# HU_MAIN_PCB_revA.net
KiCad netlist of a schematic drawn in Altium Designer
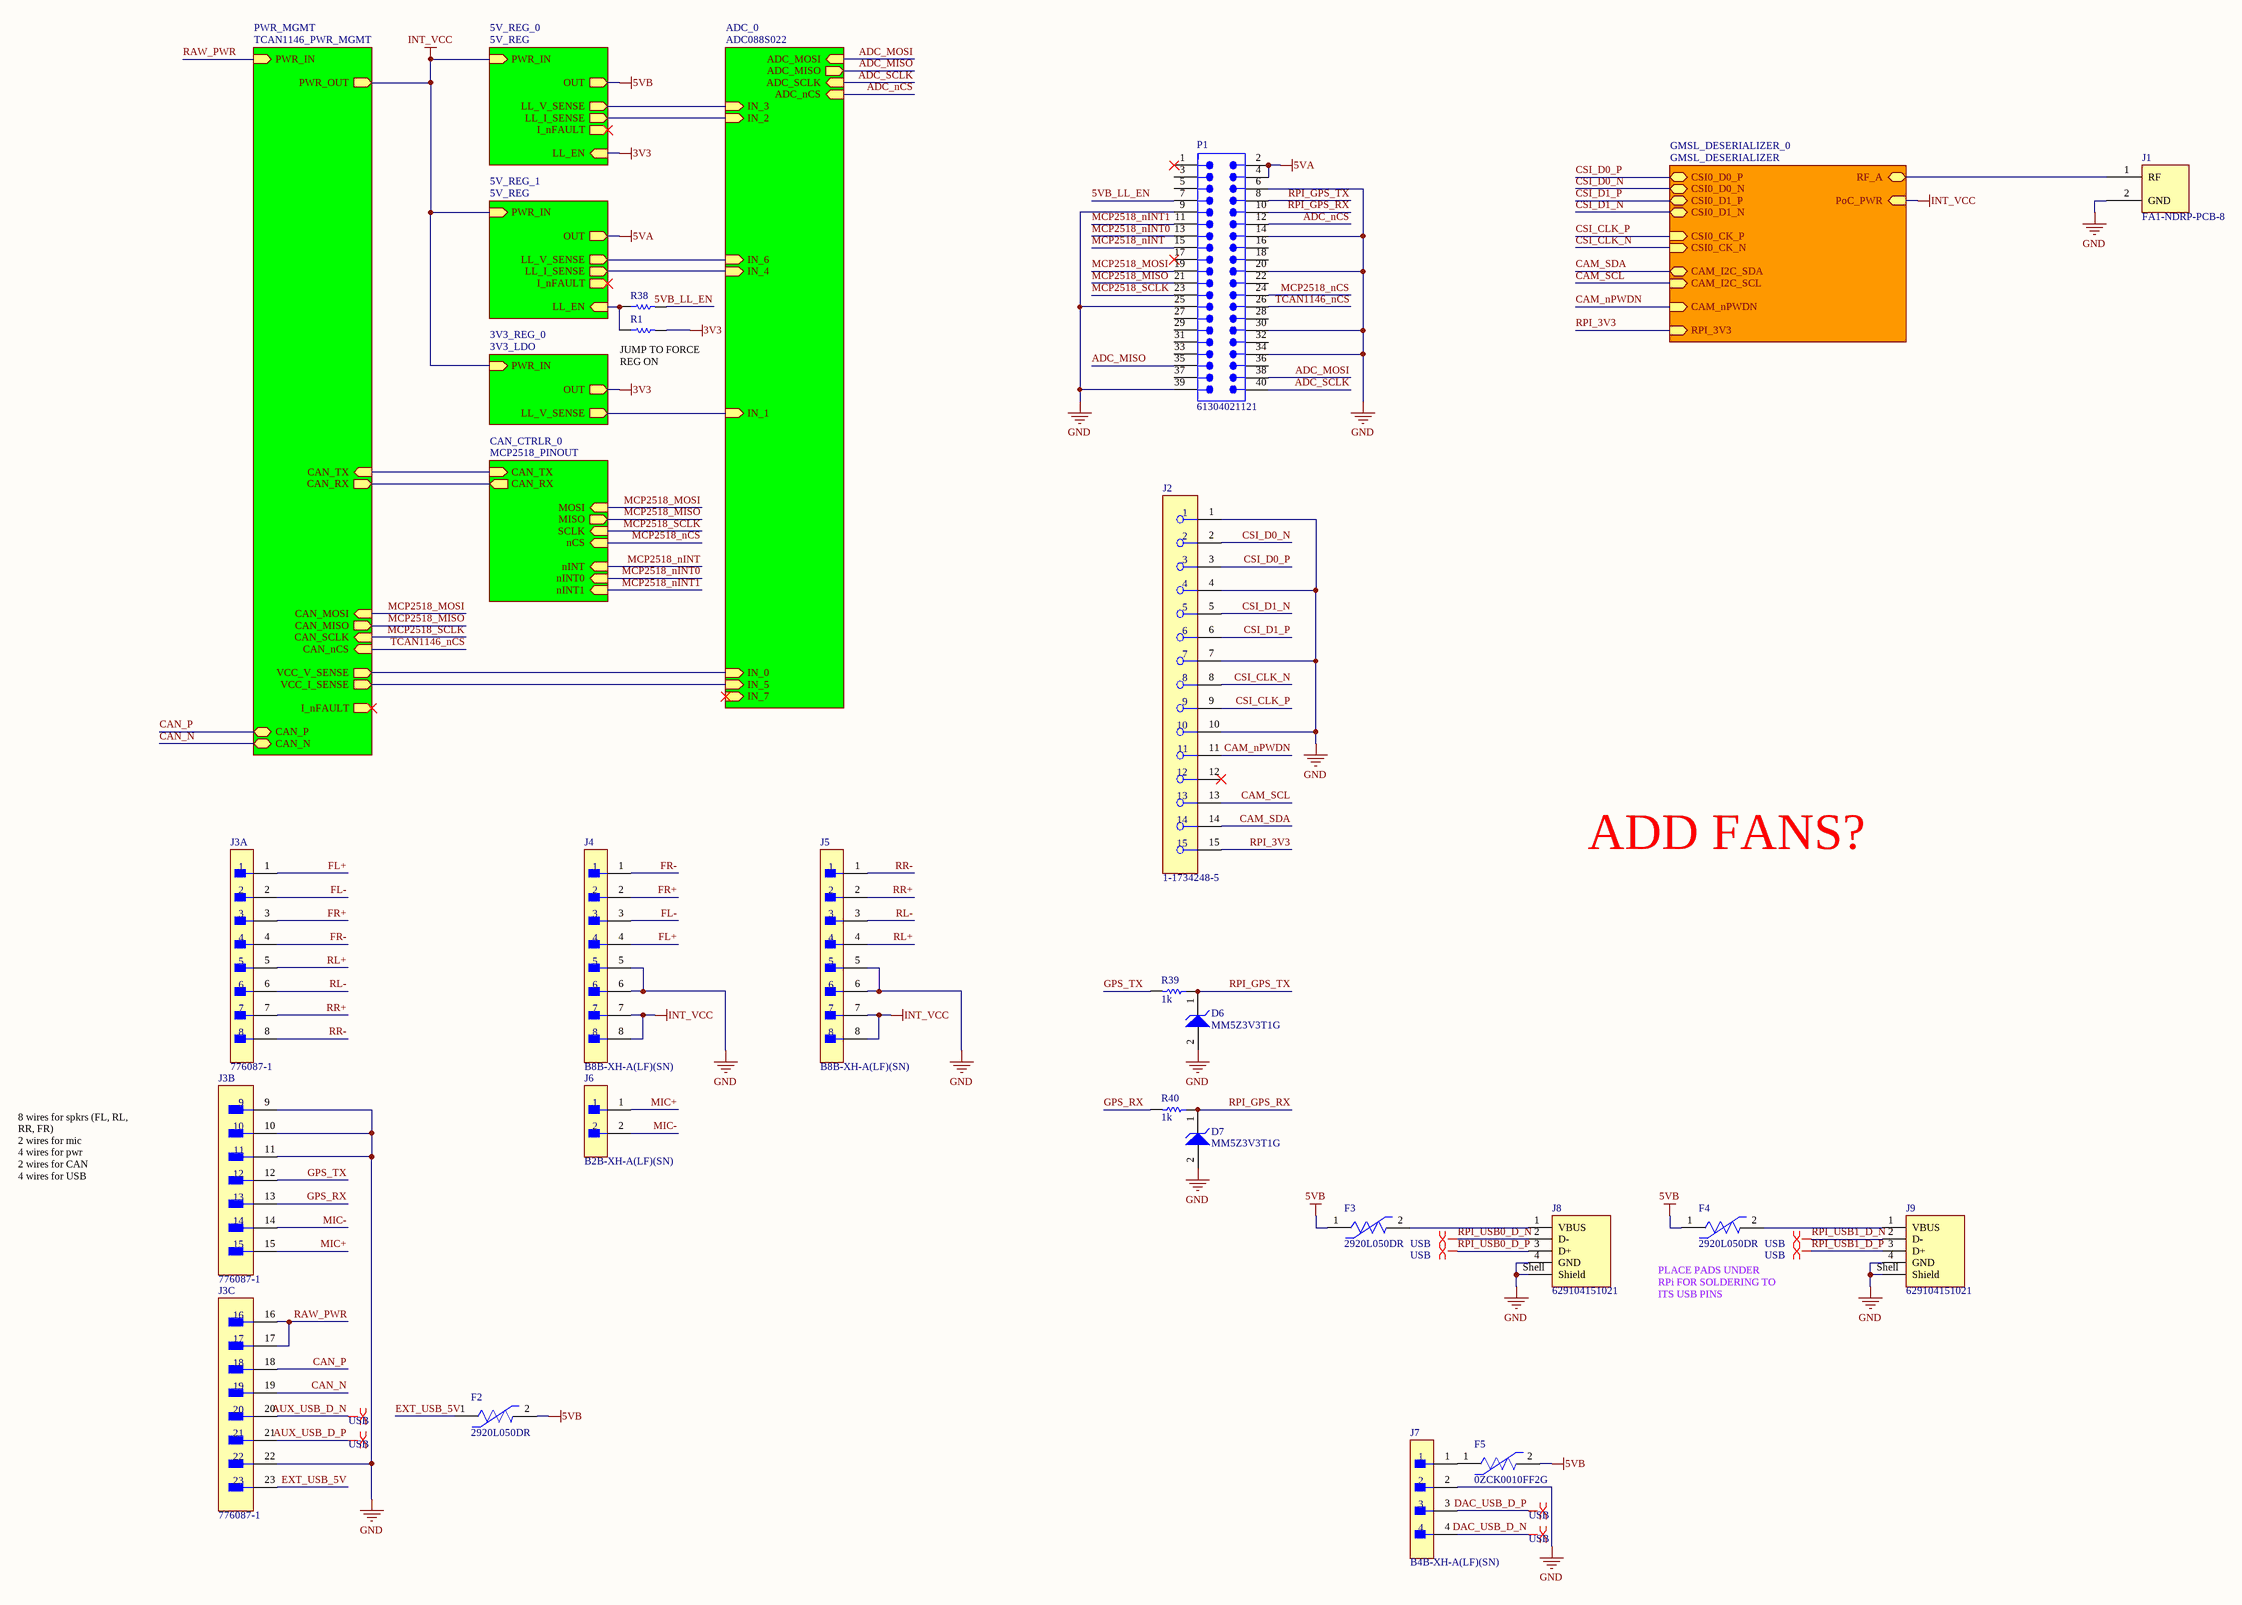
[diagram p0: HU_MAIN_PCB_revA.SchDoc]

(export (version "E")
  (design (tool "Eeschema 10.0.6"))
  (components
    (comp (ref "D6")
      (value "MM5Z3V3T1G")
      (footprint "ONSC-SOD-523-2-502-01_V")
      (description "Zener Voltage Regulator, 500 mW, 2-Pin SOD-523, Pb-Free, Tape and Reel")
      (fields (field (name "MANUFACTURER") "On Semiconductor"))
      (libsource (lib "Altium Content Vault") (part "ONSC-K1A2-2"))
    )
    (comp (ref "D7")
      (value "MM5Z3V3T1G")
      (footprint "ONSC-SOD-523-2-502-01_V")
      (description "Zener Voltage Regulator, 500 mW, 2-Pin SOD-523, Pb-Free, Tape and Reel")
      (fields (field (name "MANUFACTURER") "On Semiconductor"))
      (libsource (lib "Altium Content Vault") (part "ONSC-K1A2-2"))
    )
    (comp (ref "F2")
      (value "2920L050DR")
      (footprint "FP-2920L050DR-MFG")
      (description "PTC RESET FUSE 60V 500MA 2920")
      (libsource (lib "Altium Content Vault") (part "1c6d77a0208143737455a0c7eb396be"))
    )
    (comp (ref "F3")
      (value "2920L050DR")
      (footprint "FP-2920L050DR-MFG")
      (description "PTC RESET FUSE 60V 500MA 2920")
      (libsource (lib "Altium Content Vault") (part "1c6d77a0208143737455a0c7eb396be"))
    )
    (comp (ref "F4")
      (value "2920L050DR")
      (footprint "FP-2920L050DR-MFG")
      (description "PTC RESET FUSE 60V 500MA 2920")
      (libsource (lib "Altium Content Vault") (part "1c6d77a0208143737455a0c7eb396be"))
    )
    (comp (ref "F5")
      (value "0ZCK0010FF2G")
      (footprint "FP-0ZCK0010FF2G-MFG")
      (description "PTC RESET FUSE 15V 100MA 0805")
      (libsource (lib "Altium Content Vault") (part "fc31388045fc42ab786d6d00b506e9f"))
    )
    (comp (ref "J1")
      (value "FA1-NDRP-PCB-8")
      (footprint "FA1-NDRP-PCB-8-Footprint-1")
      (description "RF F Connector, Male, Board Mount, Solder Terminal, Plug")
      (libsource (lib "Space Concordia") (part "FA1-NDRP-PCB-8"))
    )
    (comp (ref "J2")
      (value "1-1734248-5")
      (footprint "FP-1-1734248-5-MFG")
      (description "CONN FPC VERT 15POS 1.00MM SMD")
      (fields
        (field (name "MANUFACTURER") "TE")
        (field (name "OCTOPART") "https://octopart.com/1-1734248-5-te+connectivity-40620898")
      )
      (libsource (lib "Altium Content Vault") (part "a0777be16b290adccad2a8f9338c195"))
    )
    (comp (ref "J3")
      (value "776087-1")
      (footprint "FP-776087-1-MFG")
      (description "CONN HEADER R/A 23POS 4MM")
      (libsource (lib "Altium Content Vault") (part "1cdbe6524175775e54446a79a4f0ed8"))
    )
    (comp (ref "J4")
      (value "B8B-XH-A(LF)(SN)")
      (footprint "FP-B8B-XH-A_LF_SN-MFG")
      (description "CONN HEADER VERT 8POS 2.5MM")
      (libsource (lib "Altium Content Vault") (part "99ec2b232beb5d2356d4d77f6a047f0"))
    )
    (comp (ref "J5")
      (value "B8B-XH-A(LF)(SN)")
      (footprint "FP-B8B-XH-A_LF_SN-MFG")
      (description "CONN HEADER VERT 8POS 2.5MM")
      (libsource (lib "Altium Content Vault") (part "99ec2b232beb5d2356d4d77f6a047f0"))
    )
    (comp (ref "J6")
      (value "B2B-XH-A(LF)(SN)")
      (footprint "FP-B2B-XH-A_LF_SN-MFG")
      (description "CONN HEADER VERT 2POS 2.5MM")
      (libsource (lib "Altium Content Vault") (part "3bc925449376181038e59eaffc5286c"))
    )
    (comp (ref "J7")
      (value "B4B-XH-A(LF)(SN)")
      (footprint "FP-B4B-XH-A_LF_SN-MFG")
      (description "CONN HEADER VERT 4POS 2.5MM")
      (libsource (lib "Altium Content Vault") (part "299a8cea1bdcbc3624fe62c390fa72c"))
    )
    (comp (ref "J8")
      (value "629104151021")
      (footprint "629104151021")
      (libsource (lib "Altium Content Vault") (part "USB 2.0_Type A_Receptacle_1 Port"))
    )
    (comp (ref "J9")
      (value "629104151021")
      (footprint "629104151021")
      (libsource (lib "Altium Content Vault") (part "USB 2.0_Type A_Receptacle_1 Port"))
    )
    (comp (ref "P1")
      (value "61304021121")
      (footprint "61304021121")
      (libsource (lib "Altium Content Vault") (part "Header_Male_2R_40P"))
    )
    (comp (ref "R1")
      (value "DNP")
      (footprint "RESC1005X40X25ML05T05")
      (description "READ THE NAME")
      (libsource (lib "Space Concordia") (part "CMP-009-00206-2"))
    )
    (comp (ref "R38")
      (value "DNP")
      (footprint "RESC1005X40X25ML05T05")
      (description "READ THE NAME")
      (libsource (lib "Space Concordia") (part "CMP-009-00206-2"))
    )
    (comp (ref "R39")
      (value "1k")
      (footprint "R0603B")
      (description "Resistor")
      (libsource (lib "Space Concordia") (part "Resistor"))
    )
    (comp (ref "R40")
      (value "1k")
      (footprint "R0603B")
      (description "Resistor")
      (libsource (lib "Space Concordia") (part "Resistor"))
    )
  )
  (nets
    (net (code "1") (name "/5VB_LL_EN") (class "Default")
      (node (ref "P1") (pin "7") (pinfunction "7_7") (pintype "passive"))
      (node (ref "R38") (pin "2") (pinfunction "2_2") (pintype "passive"))
    )
    (net (code "2") (name "/ADC_MISO") (class "Default")
      (node (ref "P1") (pin "35") (pinfunction "35_35") (pintype "passive"))
    )
    (net (code "3") (name "/ADC_MOSI") (class "Default")
      (node (ref "P1") (pin "38") (pinfunction "38_38") (pintype "passive"))
    )
    (net (code "4") (name "/ADC_SCLK") (class "Default")
      (node (ref "P1") (pin "40") (pinfunction "40_40") (pintype "passive"))
    )
    (net (code "5") (name "/ADC_nCS") (class "Default")
      (node (ref "P1") (pin "12") (pinfunction "12_12") (pintype "passive"))
    )
    (net (code "6") (name "/AUX_USB_D_N") (class "Default")
      (node (ref "J3") (pin "20") (pinfunction "20_20") (pintype "passive"))
    )
    (net (code "7") (name "/AUX_USB_D_P") (class "Default")
      (node (ref "J3") (pin "21") (pinfunction "21_21") (pintype "passive"))
    )
    (net (code "8") (name "/CAM_SCL") (class "Default")
      (node (ref "J2") (pin "13") (pinfunction "13_13") (pintype "passive"))
    )
    (net (code "9") (name "/CAM_SDA") (class "Default")
      (node (ref "J2") (pin "14") (pinfunction "14_14") (pintype "passive"))
    )
    (net (code "10") (name "/CAM_nPWDN") (class "Default")
      (node (ref "J2") (pin "11") (pinfunction "11_11") (pintype "passive"))
    )
    (net (code "11") (name "/CAN_N") (class "Default")
      (node (ref "J3") (pin "19") (pinfunction "19_19") (pintype "passive"))
    )
    (net (code "12") (name "/CAN_P") (class "Default")
      (node (ref "J3") (pin "18") (pinfunction "18_18") (pintype "passive"))
    )
    (net (code "15") (name "/CSI_CLK_N") (class "Default")
      (node (ref "J2") (pin "8") (pinfunction "8_8") (pintype "passive"))
    )
    (net (code "16") (name "/CSI_CLK_P") (class "Default")
      (node (ref "J2") (pin "9") (pinfunction "9_9") (pintype "passive"))
    )
    (net (code "17") (name "/CSI_D0_N") (class "Default")
      (node (ref "J2") (pin "2") (pinfunction "2_2") (pintype "passive"))
    )
    (net (code "18") (name "/CSI_D0_P") (class "Default")
      (node (ref "J2") (pin "3") (pinfunction "3_3") (pintype "passive"))
    )
    (net (code "19") (name "/CSI_D1_N") (class "Default")
      (node (ref "J2") (pin "5") (pinfunction "5_5") (pintype "passive"))
    )
    (net (code "20") (name "/CSI_D1_P") (class "Default")
      (node (ref "J2") (pin "6") (pinfunction "6_6") (pintype "passive"))
    )
    (net (code "21") (name "/DAC_USB_D_N") (class "Default")
      (node (ref "J7") (pin "4") (pinfunction "4_4") (pintype "passive"))
    )
    (net (code "22") (name "/DAC_USB_D_P") (class "Default")
      (node (ref "J7") (pin "3") (pinfunction "3_3") (pintype "passive"))
    )
    (net (code "23") (name "/EXT_USB_5V") (class "Default")
      (node (ref "F2") (pin "1") (pinfunction "1_1") (pintype "passive"))
      (node (ref "J3") (pin "23") (pinfunction "23_23") (pintype "passive"))
    )
    (net (code "24") (name "/FL+") (class "Default")
      (node (ref "J3") (pin "1") (pinfunction "1_1") (pintype "passive"))
      (node (ref "J4") (pin "4") (pinfunction "4_4") (pintype "passive"))
    )
    (net (code "25") (name "/FL-") (class "Default")
      (node (ref "J3") (pin "2") (pinfunction "2_2") (pintype "passive"))
      (node (ref "J4") (pin "3") (pinfunction "3_3") (pintype "passive"))
    )
    (net (code "26") (name "/FR+") (class "Default")
      (node (ref "J3") (pin "3") (pinfunction "3_3") (pintype "passive"))
      (node (ref "J4") (pin "2") (pinfunction "2_2") (pintype "passive"))
    )
    (net (code "27") (name "/FR-") (class "Default")
      (node (ref "J3") (pin "4") (pinfunction "4_4") (pintype "passive"))
      (node (ref "J4") (pin "1") (pinfunction "1_1") (pintype "passive"))
    )
    (net (code "28") (name "/GPS_RX") (class "Default")
      (node (ref "J3") (pin "13") (pinfunction "13_13") (pintype "passive"))
      (node (ref "R40") (pin "2") (pinfunction "2_2") (pintype "passive"))
    )
    (net (code "29") (name "/GPS_TX") (class "Default")
      (node (ref "J3") (pin "12") (pinfunction "12_12") (pintype "passive"))
      (node (ref "R39") (pin "2") (pinfunction "2_2") (pintype "passive"))
    )
    (net (code "34") (name "/LL_EN") (class "Default")
      (node (ref "R1") (pin "1") (pinfunction "1_1") (pintype "passive"))
      (node (ref "R38") (pin "1") (pinfunction "1_1") (pintype "passive"))
    )
    (net (code "40") (name "/MCP2518_MISO") (class "Default")
      (node (ref "P1") (pin "21") (pinfunction "21_21") (pintype "passive"))
    )
    (net (code "41") (name "/MCP2518_MOSI") (class "Default")
      (node (ref "P1") (pin "19") (pinfunction "19_19") (pintype "passive"))
    )
    (net (code "42") (name "/MCP2518_SCLK") (class "Default")
      (node (ref "P1") (pin "23") (pinfunction "23_23") (pintype "passive"))
    )
    (net (code "43") (name "/MCP2518_nCS") (class "Default")
      (node (ref "P1") (pin "24") (pinfunction "24_24") (pintype "passive"))
    )
    (net (code "44") (name "/MCP2518_nINT") (class "Default")
      (node (ref "P1") (pin "15") (pinfunction "15_15") (pintype "passive"))
    )
    (net (code "45") (name "/MCP2518_nINT0") (class "Default")
      (node (ref "P1") (pin "13") (pinfunction "13_13") (pintype "passive"))
    )
    (net (code "46") (name "/MCP2518_nINT1") (class "Default")
      (node (ref "P1") (pin "11") (pinfunction "11_11") (pintype "passive"))
    )
    (net (code "47") (name "/MIC+") (class "Default")
      (node (ref "J3") (pin "15") (pinfunction "15_15") (pintype "passive"))
      (node (ref "J6") (pin "1") (pinfunction "1_1") (pintype "passive"))
    )
    (net (code "48") (name "/MIC-") (class "Default")
      (node (ref "J3") (pin "14") (pinfunction "14_14") (pintype "passive"))
      (node (ref "J6") (pin "2") (pinfunction "2_2") (pintype "passive"))
    )
    (net (code "49") (name "/RAW_PWR") (class "Default")
      (node (ref "J3") (pin "16") (pinfunction "16_16") (pintype "passive"))
      (node (ref "J3") (pin "17") (pinfunction "17_17") (pintype "passive"))
    )
    (net (code "50") (name "/RF_A") (class "Default")
      (node (ref "J1") (pin "1") (pinfunction "RF_1") (pintype "passive"))
    )
    (net (code "51") (name "/RL+") (class "Default")
      (node (ref "J3") (pin "5") (pinfunction "5_5") (pintype "passive"))
      (node (ref "J5") (pin "4") (pinfunction "4_4") (pintype "passive"))
    )
    (net (code "52") (name "/RL-") (class "Default")
      (node (ref "J3") (pin "6") (pinfunction "6_6") (pintype "passive"))
      (node (ref "J5") (pin "3") (pinfunction "3_3") (pintype "passive"))
    )
    (net (code "53") (name "/RPI_3V3") (class "Default")
      (node (ref "J2") (pin "15") (pinfunction "15_15") (pintype "passive"))
    )
    (net (code "54") (name "/RPI_GPS_RX") (class "Default")
      (node (ref "D7") (pin "1") (pinfunction "K_1") (pintype "passive"))
      (node (ref "P1") (pin "10") (pinfunction "10_10") (pintype "passive"))
      (node (ref "R40") (pin "1") (pinfunction "1_1") (pintype "passive"))
    )
    (net (code "55") (name "/RPI_GPS_TX") (class "Default")
      (node (ref "D6") (pin "1") (pinfunction "K_1") (pintype "passive"))
      (node (ref "P1") (pin "8") (pinfunction "8_8") (pintype "passive"))
      (node (ref "R39") (pin "1") (pinfunction "1_1") (pintype "passive"))
    )
    (net (code "56") (name "/RPI_USB0_D_N") (class "Default")
      (node (ref "J8") (pin "2") (pinfunction "D-_2") (pintype "passive"))
    )
    (net (code "57") (name "/RPI_USB0_D_P") (class "Default")
      (node (ref "J8") (pin "3") (pinfunction "D+_3") (pintype "passive"))
    )
    (net (code "58") (name "/RPI_USB1_D_N") (class "Default")
      (node (ref "J9") (pin "2") (pinfunction "D-_2") (pintype "passive"))
    )
    (net (code "59") (name "/RPI_USB1_D_P") (class "Default")
      (node (ref "J9") (pin "3") (pinfunction "D+_3") (pintype "passive"))
    )
    (net (code "60") (name "/RR+") (class "Default")
      (node (ref "J3") (pin "7") (pinfunction "7_7") (pintype "passive"))
      (node (ref "J5") (pin "2") (pinfunction "2_2") (pintype "passive"))
    )
    (net (code "61") (name "/RR-") (class "Default")
      (node (ref "J3") (pin "8") (pinfunction "8_8") (pintype "passive"))
      (node (ref "J5") (pin "1") (pinfunction "1_1") (pintype "passive"))
    )
    (net (code "62") (name "/TCAN1146_nCS") (class "Default")
      (node (ref "P1") (pin "26") (pinfunction "26_26") (pintype "passive"))
    )
    (net (code "65") (name "3V3") (class "Default")
      (node (ref "R1") (pin "2") (pinfunction "2_2") (pintype "passive"))
    )
    (net (code "66") (name "5VA") (class "Default")
      (node (ref "P1") (pin "2") (pinfunction "2_2") (pintype "passive"))
      (node (ref "P1") (pin "4") (pinfunction "4_4") (pintype "passive"))
    )
    (net (code "67") (name "5VB") (class "Default")
      (node (ref "F2") (pin "2") (pinfunction "2_2") (pintype "passive"))
      (node (ref "F3") (pin "1") (pinfunction "1_1") (pintype "passive"))
      (node (ref "F4") (pin "1") (pinfunction "1_1") (pintype "passive"))
      (node (ref "F5") (pin "2") (pinfunction "2_2") (pintype "passive"))
    )
    (net (code "68") (name "GND") (class "Default")
      (node (ref "D6") (pin "2") (pinfunction "A_2") (pintype "passive"))
      (node (ref "D7") (pin "2") (pinfunction "A_2") (pintype "passive"))
      (node (ref "J1") (pin "2") (pinfunction "GND_2") (pintype "passive"))
      (node (ref "J2") (pin "1") (pinfunction "1_1") (pintype "passive"))
      (node (ref "J2") (pin "10") (pinfunction "10_10") (pintype "passive"))
      (node (ref "J2") (pin "4") (pinfunction "4_4") (pintype "passive"))
      (node (ref "J2") (pin "7") (pinfunction "7_7") (pintype "passive"))
      (node (ref "J3") (pin "10") (pinfunction "10_10") (pintype "passive"))
      (node (ref "J3") (pin "11") (pinfunction "11_11") (pintype "passive"))
      (node (ref "J3") (pin "22") (pinfunction "22_22") (pintype "passive"))
      (node (ref "J3") (pin "9") (pinfunction "9_9") (pintype "passive"))
      (node (ref "J4") (pin "5") (pinfunction "5_5") (pintype "passive"))
      (node (ref "J4") (pin "6") (pinfunction "6_6") (pintype "passive"))
      (node (ref "J5") (pin "5") (pinfunction "5_5") (pintype "passive"))
      (node (ref "J5") (pin "6") (pinfunction "6_6") (pintype "passive"))
      (node (ref "J7") (pin "2") (pinfunction "2_2") (pintype "passive"))
      (node (ref "J8") (pin "4") (pinfunction "GND_4") (pintype "passive"))
      (node (ref "J8") (pin "Shell") (pinfunction "Shield_Shell") (pintype "passive"))
      (node (ref "J9") (pin "4") (pinfunction "GND_4") (pintype "passive"))
      (node (ref "J9") (pin "Shell") (pinfunction "Shield_Shell") (pintype "passive"))
      (node (ref "P1") (pin "14") (pinfunction "14_14") (pintype "passive"))
      (node (ref "P1") (pin "20") (pinfunction "20_20") (pintype "passive"))
      (node (ref "P1") (pin "25") (pinfunction "25_25") (pintype "passive"))
      (node (ref "P1") (pin "30") (pinfunction "30_30") (pintype "passive"))
      (node (ref "P1") (pin "34") (pinfunction "34_34") (pintype "passive"))
      (node (ref "P1") (pin "39") (pinfunction "39_39") (pintype "passive"))
      (node (ref "P1") (pin "6") (pinfunction "6_6") (pintype "passive"))
      (node (ref "P1") (pin "9") (pinfunction "9_9") (pintype "passive"))
    )
    (net (code "69") (name "INT_VCC") (class "Default")
      (node (ref "J4") (pin "7") (pinfunction "7_7") (pintype "passive"))
      (node (ref "J4") (pin "8") (pinfunction "8_8") (pintype "passive"))
      (node (ref "J5") (pin "7") (pinfunction "7_7") (pintype "passive"))
      (node (ref "J5") (pin "8") (pinfunction "8_8") (pintype "passive"))
    )
    (net (code "70") (name "Net-(F5-Pad1)") (class "Default")
      (node (ref "F5") (pin "1") (pinfunction "1_1") (pintype "passive"))
      (node (ref "J7") (pin "1") (pinfunction "1_1") (pintype "passive"))
    )
    (net (code "71") (name "Net-(J8-VBUS)") (class "Default")
      (node (ref "F3") (pin "2") (pinfunction "2_2") (pintype "passive"))
      (node (ref "J8") (pin "1") (pinfunction "VBUS_1") (pintype "passive"))
    )
    (net (code "72") (name "Net-(J9-VBUS)") (class "Default")
      (node (ref "F4") (pin "2") (pinfunction "2_2") (pintype "passive"))
      (node (ref "J9") (pin "1") (pinfunction "VBUS_1") (pintype "passive"))
    )
    (net (code "73") (name "unconnected-(J2-Pad12)") (class "Default")
      (node (ref "J2") (pin "12") (pinfunction "12_12") (pintype "passive+no_connect"))
    )
    (net (code "74") (name "unconnected-(P1-Pad1)") (class "Default")
      (node (ref "P1") (pin "1") (pinfunction "1_1") (pintype "passive+no_connect"))
    )
    (net (code "75") (name "unconnected-(P1-Pad3)") (class "Default")
      (node (ref "P1") (pin "3") (pinfunction "3_3") (pintype "passive"))
    )
    (net (code "76") (name "unconnected-(P1-Pad5)") (class "Default")
      (node (ref "P1") (pin "5") (pinfunction "5_5") (pintype "passive"))
    )
    (net (code "77") (name "unconnected-(P1-Pad16)") (class "Default")
      (node (ref "P1") (pin "16") (pinfunction "16_16") (pintype "passive"))
    )
    (net (code "78") (name "unconnected-(P1-Pad17)") (class "Default")
      (node (ref "P1") (pin "17") (pinfunction "17_17") (pintype "passive+no_connect"))
    )
    (net (code "79") (name "unconnected-(P1-Pad18)") (class "Default")
      (node (ref "P1") (pin "18") (pinfunction "18_18") (pintype "passive"))
    )
    (net (code "80") (name "unconnected-(P1-Pad22)") (class "Default")
      (node (ref "P1") (pin "22") (pinfunction "22_22") (pintype "passive"))
    )
    (net (code "81") (name "unconnected-(P1-Pad27)") (class "Default")
      (node (ref "P1") (pin "27") (pinfunction "27_27") (pintype "passive"))
    )
    (net (code "82") (name "unconnected-(P1-Pad28)") (class "Default")
      (node (ref "P1") (pin "28") (pinfunction "28_28") (pintype "passive"))
    )
    (net (code "83") (name "unconnected-(P1-Pad29)") (class "Default")
      (node (ref "P1") (pin "29") (pinfunction "29_29") (pintype "passive"))
    )
    (net (code "84") (name "unconnected-(P1-Pad31)") (class "Default")
      (node (ref "P1") (pin "31") (pinfunction "31_31") (pintype "passive"))
    )
    (net (code "85") (name "unconnected-(P1-Pad32)") (class "Default")
      (node (ref "P1") (pin "32") (pinfunction "32_32") (pintype "passive"))
    )
    (net (code "86") (name "unconnected-(P1-Pad33)") (class "Default")
      (node (ref "P1") (pin "33") (pinfunction "33_33") (pintype "passive"))
    )
    (net (code "87") (name "unconnected-(P1-Pad36)") (class "Default")
      (node (ref "P1") (pin "36") (pinfunction "36_36") (pintype "passive"))
    )
    (net (code "88") (name "unconnected-(P1-Pad37)") (class "Default")
      (node (ref "P1") (pin "37") (pinfunction "37_37") (pintype "passive"))
    )
  )
)
